# CAN.net
KiCad netlist of a schematic drawn in Altium Designer
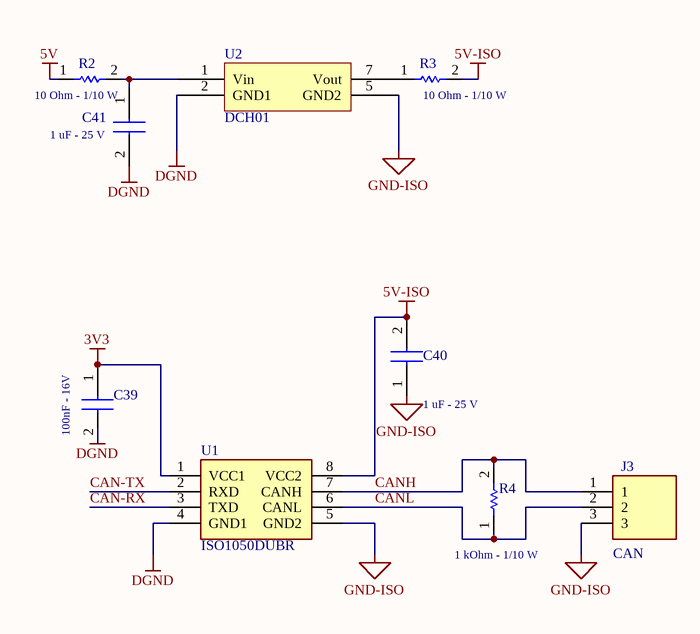
[diagram p0: CAN.SchDoc]

(export (version "E")
  (design (tool "Eeschema 10.0.6"))
  (components
    (comp (ref "C39")
      (value "100nF - 16V")
      (footprint "CAPC1608X95N")
      (description "Capacitor")
      (fields
        (field (name "MANUFACTURER_PART_NUMBER") "EMK107B7104KA-T")
        (field (name "MOUSER PART NUMBER") "963-EMK107B7104KA-T")
      )
      (libsource (lib "SamacSys") (part "EMK107B7104KA-T"))
    )
    (comp (ref "C40")
      (value "1 uF - 25 V")
      (footprint "SamacSys:CAPC2012X135N")
      (description "Capacitor")
      (fields
        (field (name "MANUFACTURER_PART_NUMBER") "CL21B105KAFNNNG")
        (field (name "MOUSER PART NUMBER") "187-CL21B105KAFNNNG")
      )
      (libsource (lib "SamacSys") (part "CL21B105KAFNNNG"))
    )
    (comp (ref "C41")
      (value "1 uF - 25 V")
      (footprint "SamacSys:CAPC2012X135N")
      (description "Capacitor")
      (fields
        (field (name "MANUFACTURER_PART_NUMBER") "CL21B105KAFNNNG")
        (field (name "MOUSER PART NUMBER") "187-CL21B105KAFNNNG")
      )
      (libsource (lib "SamacSys") (part "CL21B105KAFNNNG"))
    )
    (comp (ref "J3")
      (value "CAN")
      (footprint "76384303LF")
      (description "Connector")
      (fields
        (field (name "MANUFACTURER_PART_NUMBER") "76384-303LF")
        (field (name "MOUSER PART NUMBER") "649-76384-303LF")
      )
      (libsource (lib "SamacSys") (part "76384-303LF"))
    )
    (comp (ref "R2")
      (value "10 Ohm - 1/10 W")
      (footprint "RESC1608X50N")
      (description "Resistor")
      (fields
        (field (name "MANUFACTURER_PART_NUMBER") "CRCW060310R0FKEAHP")
        (field (name "MOUSER PART NUMBER") "71-CRCW060310R0FKEAH")
      )
      (libsource (lib "SamacSys") (part "CRCW060310R0FKEAHP"))
    )
    (comp (ref "R3")
      (value "10 Ohm - 1/10 W")
      (footprint "RESC1608X50N")
      (description "Resistor")
      (fields
        (field (name "MANUFACTURER_PART_NUMBER") "CRCW060310R0FKEAHP")
        (field (name "MOUSER PART NUMBER") "71-CRCW060310R0FKEAH")
      )
      (libsource (lib "SamacSys") (part "CRCW060310R0FKEAHP"))
    )
    (comp (ref "R4")
      (value "1 kOhm - 1/10 W")
      (footprint "RESC1608X55N")
      (description "Resistor")
      (fields
        (field (name "MANUFACTURER_PART_NUMBER") "CRCW06031K00FKEAC")
        (field (name "MOUSER PART NUMBER") "71-CRCW06031K00FKEAC")
      )
      (libsource (lib "SamacSys") (part "CRCW06031K00FKEAC"))
    )
    (comp (ref "U1")
      (value "ISO1050DUBR")
      (footprint "SOP254P1040X485-8N")
      (description "Integrated Circuit")
      (fields (field (name "MOUSER PART NUMBER") "595-ISO1050DUBR"))
      (libsource (lib "*") (part "ISO1050DUBR"))
    )
    (comp (ref "U2") (value "DCH01") (footprint "DCH01") (libsource (lib "Componentes") (part "DCH01")))
  )
  (nets
    (net (code "1") (name "/CAN-RX") (class "Default")
      (node (ref "U1") (pin "3") (pinfunction "TXD_3") (pintype "passive"))
    )
    (net (code "2") (name "/CAN-TX") (class "Default")
      (node (ref "U1") (pin "2") (pinfunction "RXD_2") (pintype "passive"))
    )
    (net (code "3") (name "/CANH") (class "Default")
      (node (ref "J3") (pin "1") (pinfunction "1_1") (pintype "passive"))
      (node (ref "R4") (pin "2") (pinfunction "2_2") (pintype "passive"))
      (node (ref "U1") (pin "7") (pinfunction "CANH_7") (pintype "passive"))
    )
    (net (code "4") (name "/CANL") (class "Default")
      (node (ref "J3") (pin "2") (pinfunction "2_2") (pintype "passive"))
      (node (ref "R4") (pin "1") (pinfunction "1_1") (pintype "passive"))
      (node (ref "U1") (pin "6") (pinfunction "CANL_6") (pintype "passive"))
    )
    (net (code "5") (name "3V3") (class "Default")
      (node (ref "C39") (pin "1") (pinfunction "1_1") (pintype "passive"))
      (node (ref "U1") (pin "1") (pinfunction "VCC1_1") (pintype "passive"))
    )
    (net (code "6") (name "5V") (class "Default")
      (node (ref "R2") (pin "1") (pinfunction "1_1") (pintype "passive"))
    )
    (net (code "7") (name "5V-ISO") (class "Default")
      (node (ref "C40") (pin "2") (pinfunction "2_2") (pintype "passive"))
      (node (ref "R3") (pin "2") (pinfunction "2_2") (pintype "passive"))
      (node (ref "U1") (pin "8") (pinfunction "VCC2_8") (pintype "passive"))
    )
    (net (code "8") (name "DGND") (class "Default")
      (node (ref "C39") (pin "2") (pinfunction "2_2") (pintype "passive"))
      (node (ref "C41") (pin "2") (pinfunction "2_2") (pintype "passive"))
      (node (ref "U1") (pin "4") (pinfunction "GND1_4") (pintype "passive"))
      (node (ref "U2") (pin "2") (pinfunction "GND1_2") (pintype "passive"))
    )
    (net (code "9") (name "GND-ISO") (class "Default")
      (node (ref "C40") (pin "1") (pinfunction "1_1") (pintype "passive"))
      (node (ref "J3") (pin "3") (pinfunction "3_3") (pintype "passive"))
      (node (ref "U1") (pin "5") (pinfunction "GND2_5") (pintype "passive"))
      (node (ref "U2") (pin "5") (pinfunction "GND2_5") (pintype "passive"))
    )
    (net (code "10") (name "Net-(U2-Vin)") (class "Default")
      (node (ref "C41") (pin "1") (pinfunction "1_1") (pintype "passive"))
      (node (ref "R2") (pin "2") (pinfunction "2_2") (pintype "passive"))
      (node (ref "U2") (pin "1") (pinfunction "Vin_1") (pintype "passive"))
    )
    (net (code "11") (name "Net-(U2-Vout)") (class "Default")
      (node (ref "R3") (pin "1") (pinfunction "1_1") (pintype "passive"))
      (node (ref "U2") (pin "7") (pinfunction "Vout_7") (pintype "passive"))
    )
  )
)
